# FPGA_IO.net
KiCad netlist of a schematic drawn in Altium Designer
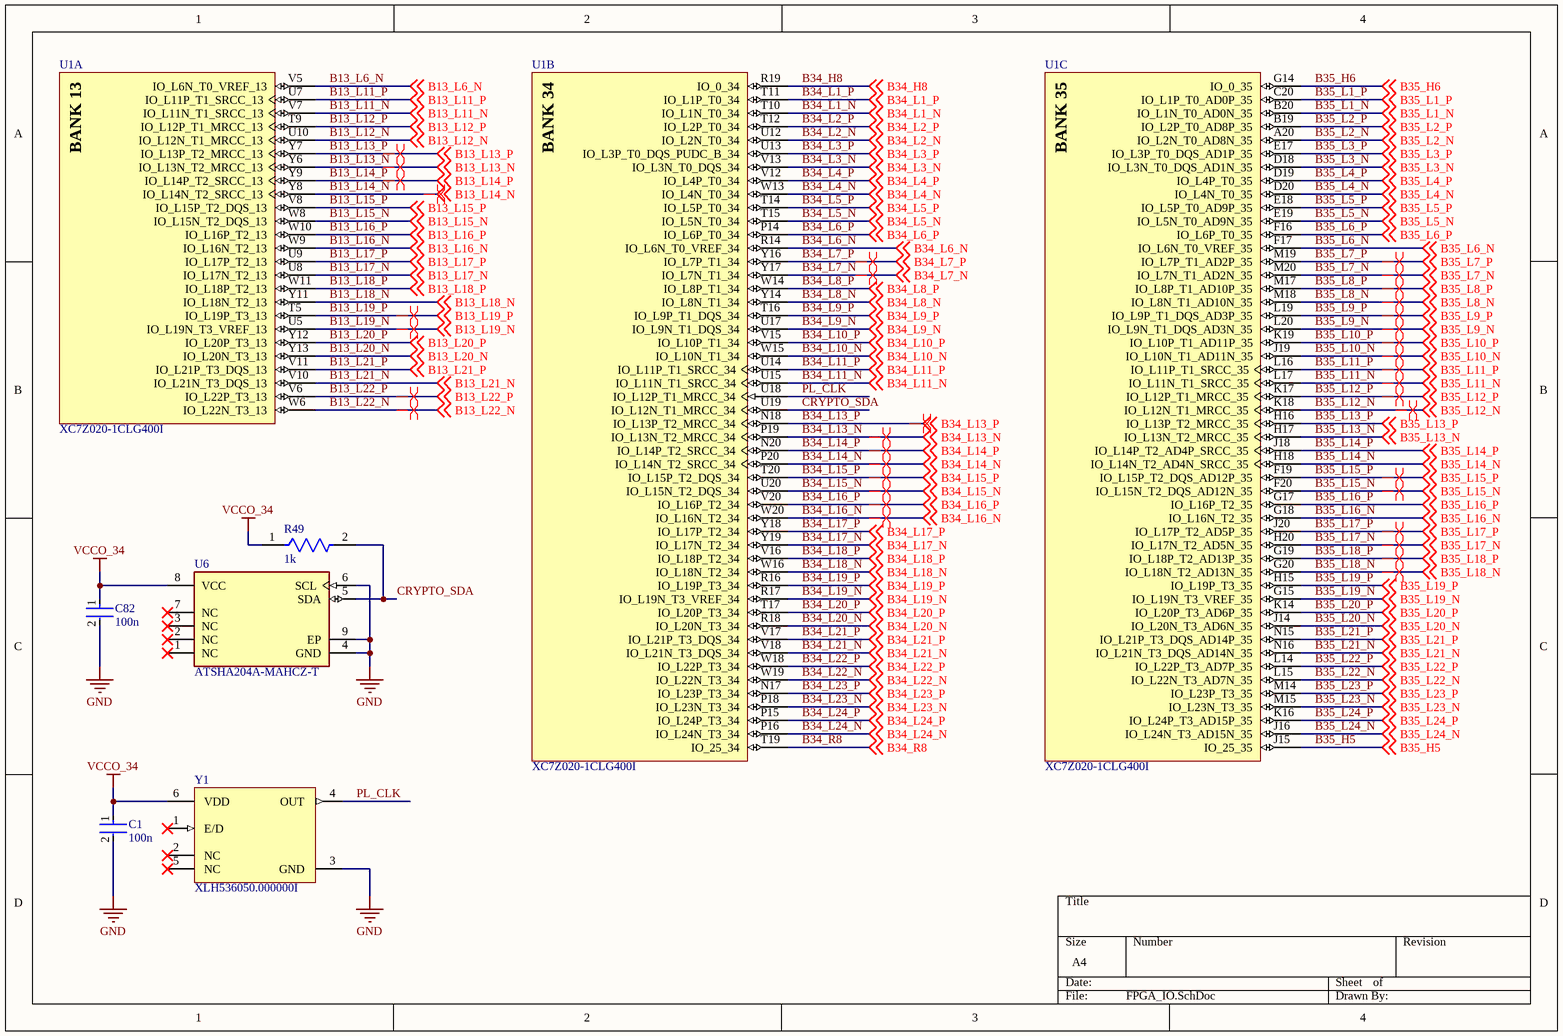
[diagram p0: FPGA_IO.SchDoc]

(export (version "E")
  (design (tool "Eeschema 10.0.6"))
  (components
    (comp (ref "C1")
      (value "100n")
      (footprint "FP-CC0603-DA-MFG")
      (description "CAP CER 0.1UF 50V X7R 0603")
      (fields (field (name "MANUFACTURER") "YAGEO") (field (name "VOLTAGE") "50 V"))
      (libsource (lib "Altium Content Vault") (part "11868f565c42a9108669ba33697ecf6"))
    )
    (comp (ref "C82")
      (value "100n")
      (footprint "FP-CC0603-DA-MFG")
      (description "CAP CER 0.1UF 50V X7R 0603")
      (fields (field (name "MANUFACTURER") "YAGEO") (field (name "VOLTAGE") "50 V"))
      (libsource (lib "Altium Content Vault") (part "11868f565c42a9108669ba33697ecf6"))
    )
    (comp (ref "R49")
      (value "1k")
      (footprint "FP-RC0603-0_55-IPC_C")
      (description "RES 1K OHM 1% 1/10W 0603")
      (fields (field (name "TOLERANCE") "1%"))
      (libsource (lib "Altium Content Vault") (part "1029c3af85768c4190bb7ad29bc67b5"))
    )
    (comp (ref "U1")
      (value "XC7Z020-1CLG400I")
      (footprint "CLG400")
      (fields (field (name "GENERIC PART NUMBER") "XC7Z020"))
      (libsource (lib "Altium Content Vault") (part "XNLX-XC7Z020-CLG400"))
    )
    (comp (ref "U6")
      (value "ATSHA204A-MAHCZ-T")
      (footprint "FP-C04-21355-Q4B-MFG")
      (description "IC AUTHENTICATION CHIP 8UDFN")
      (libsource (lib "Altium Content Vault") (part "d8c86bdfd731f46be08b2b7a0237097"))
    )
    (comp (ref "Y1")
      (value "XLH536050.000000I")
      (footprint "JS6_MFG")
      (description "Oscillator Xo 50MHZ ±25PPM 15PF Hcmos 55% 3.3V 6-PIN Cllcc SMD T/r")
      (libsource (lib "Altium Content Vault") (part "c6c94343aa228214f04837505267066"))
    )
  )
  (nets
    (net (code "1") (name "/CRYPTO_SDA") (class "Default")
      (node (ref "R49") (pin "2") (pinfunction "2_2") (pintype "passive"))
      (node (ref "U1") (pin "U19") (pinfunction "IO_L12N_T1_MRCC_34_U19") (pintype "bidirectional"))
      (node (ref "U6") (pin "5") (pinfunction "SDA_5") (pintype "bidirectional"))
    )
    (net (code "2") (name "/PL_CLK") (class "Default")
      (node (ref "U1") (pin "U18") (pinfunction "IO_L12P_T1_MRCC_34_U18") (pintype "bidirectional"))
      (node (ref "Y1") (pin "4") (pinfunction "OUT_4") (pintype "output"))
    )
    (net (code "3") (name "B13_L6_N") (class "Default")
      (node (ref "U1") (pin "V5") (pinfunction "IO_L6N_T0_VREF_13_V5") (pintype "bidirectional"))
    )
    (net (code "4") (name "B13_L11_N") (class "Default")
      (node (ref "U1") (pin "V7") (pinfunction "IO_L11N_T1_SRCC_13_V7") (pintype "bidirectional"))
    )
    (net (code "5") (name "B13_L11_P") (class "Default")
      (node (ref "U1") (pin "U7") (pinfunction "IO_L11P_T1_SRCC_13_U7") (pintype "bidirectional"))
    )
    (net (code "6") (name "B13_L12_N") (class "Default")
      (node (ref "U1") (pin "U10") (pinfunction "IO_L12N_T1_MRCC_13_U10") (pintype "bidirectional"))
    )
    (net (code "7") (name "B13_L12_P") (class "Default")
      (node (ref "U1") (pin "T9") (pinfunction "IO_L12P_T1_MRCC_13_T9") (pintype "bidirectional"))
    )
    (net (code "8") (name "B13_L13_N") (class "Default")
      (node (ref "U1") (pin "Y6") (pinfunction "IO_L13N_T2_MRCC_13_Y6") (pintype "bidirectional"))
    )
    (net (code "9") (name "B13_L13_P") (class "Default")
      (node (ref "U1") (pin "Y7") (pinfunction "IO_L13P_T2_MRCC_13_Y7") (pintype "bidirectional"))
    )
    (net (code "10") (name "B13_L14_N") (class "Default")
      (node (ref "U1") (pin "Y8") (pinfunction "IO_L14N_T2_SRCC_13_Y8") (pintype "bidirectional"))
    )
    (net (code "11") (name "B13_L14_P") (class "Default")
      (node (ref "U1") (pin "Y9") (pinfunction "IO_L14P_T2_SRCC_13_Y9") (pintype "bidirectional"))
    )
    (net (code "12") (name "B13_L15_N") (class "Default")
      (node (ref "U1") (pin "W8") (pinfunction "IO_L15N_T2_DQS_13_W8") (pintype "bidirectional"))
    )
    (net (code "13") (name "B13_L15_P") (class "Default")
      (node (ref "U1") (pin "V8") (pinfunction "IO_L15P_T2_DQS_13_V8") (pintype "bidirectional"))
    )
    (net (code "14") (name "B13_L16_N") (class "Default")
      (node (ref "U1") (pin "W9") (pinfunction "IO_L16N_T2_13_W9") (pintype "bidirectional"))
    )
    (net (code "15") (name "B13_L16_P") (class "Default")
      (node (ref "U1") (pin "W10") (pinfunction "IO_L16P_T2_13_W10") (pintype "bidirectional"))
    )
    (net (code "16") (name "B13_L17_N") (class "Default")
      (node (ref "U1") (pin "U8") (pinfunction "IO_L17N_T2_13_U8") (pintype "bidirectional"))
    )
    (net (code "17") (name "B13_L17_P") (class "Default")
      (node (ref "U1") (pin "U9") (pinfunction "IO_L17P_T2_13_U9") (pintype "bidirectional"))
    )
    (net (code "18") (name "B13_L18_N") (class "Default")
      (node (ref "U1") (pin "Y11") (pinfunction "IO_L18N_T2_13_Y11") (pintype "bidirectional"))
    )
    (net (code "19") (name "B13_L18_P") (class "Default")
      (node (ref "U1") (pin "W11") (pinfunction "IO_L18P_T2_13_W11") (pintype "bidirectional"))
    )
    (net (code "20") (name "B13_L19_N") (class "Default")
      (node (ref "U1") (pin "U5") (pinfunction "IO_L19N_T3_VREF_13_U5") (pintype "bidirectional"))
    )
    (net (code "21") (name "B13_L19_P") (class "Default")
      (node (ref "U1") (pin "T5") (pinfunction "IO_L19P_T3_13_T5") (pintype "bidirectional"))
    )
    (net (code "22") (name "B13_L20_N") (class "Default")
      (node (ref "U1") (pin "Y13") (pinfunction "IO_L20N_T3_13_Y13") (pintype "bidirectional"))
    )
    (net (code "23") (name "B13_L20_P") (class "Default")
      (node (ref "U1") (pin "Y12") (pinfunction "IO_L20P_T3_13_Y12") (pintype "bidirectional"))
    )
    (net (code "24") (name "B13_L21_N") (class "Default")
      (node (ref "U1") (pin "V10") (pinfunction "IO_L21N_T3_DQS_13_V10") (pintype "bidirectional"))
    )
    (net (code "25") (name "B13_L21_P") (class "Default")
      (node (ref "U1") (pin "V11") (pinfunction "IO_L21P_T3_DQS_13_V11") (pintype "bidirectional"))
    )
    (net (code "26") (name "B13_L22_N") (class "Default")
      (node (ref "U1") (pin "W6") (pinfunction "IO_L22N_T3_13_W6") (pintype "bidirectional"))
    )
    (net (code "27") (name "B13_L22_P") (class "Default")
      (node (ref "U1") (pin "V6") (pinfunction "IO_L22P_T3_13_V6") (pintype "bidirectional"))
    )
    (net (code "28") (name "B34_H8") (class "Default")
      (node (ref "U1") (pin "R19") (pinfunction "IO_0_34_R19") (pintype "bidirectional"))
    )
    (net (code "29") (name "B34_L1_N") (class "Default")
      (node (ref "U1") (pin "T10") (pinfunction "IO_L1N_T0_34_T10") (pintype "bidirectional"))
    )
    (net (code "30") (name "B34_L1_P") (class "Default")
      (node (ref "U1") (pin "T11") (pinfunction "IO_L1P_T0_34_T11") (pintype "bidirectional"))
    )
    (net (code "31") (name "B34_L2_N") (class "Default")
      (node (ref "U1") (pin "U12") (pinfunction "IO_L2N_T0_34_U12") (pintype "bidirectional"))
    )
    (net (code "32") (name "B34_L2_P") (class "Default")
      (node (ref "U1") (pin "T12") (pinfunction "IO_L2P_T0_34_T12") (pintype "bidirectional"))
    )
    (net (code "33") (name "B34_L3_N") (class "Default")
      (node (ref "U1") (pin "V13") (pinfunction "IO_L3N_T0_DQS_34_V13") (pintype "bidirectional"))
    )
    (net (code "34") (name "B34_L3_P") (class "Default")
      (node (ref "U1") (pin "U13") (pinfunction "IO_L3P_T0_DQS_PUDC_B_34_U13") (pintype "bidirectional"))
    )
    (net (code "35") (name "B34_L4_N") (class "Default")
      (node (ref "U1") (pin "W13") (pinfunction "IO_L4N_T0_34_W13") (pintype "bidirectional"))
    )
    (net (code "36") (name "B34_L4_P") (class "Default")
      (node (ref "U1") (pin "V12") (pinfunction "IO_L4P_T0_34_V12") (pintype "bidirectional"))
    )
    (net (code "37") (name "B34_L5_N") (class "Default")
      (node (ref "U1") (pin "T15") (pinfunction "IO_L5N_T0_34_T15") (pintype "bidirectional"))
    )
    (net (code "38") (name "B34_L5_P") (class "Default")
      (node (ref "U1") (pin "T14") (pinfunction "IO_L5P_T0_34_T14") (pintype "bidirectional"))
    )
    (net (code "39") (name "B34_L6_N") (class "Default")
      (node (ref "U1") (pin "R14") (pinfunction "IO_L6N_T0_VREF_34_R14") (pintype "bidirectional"))
    )
    (net (code "40") (name "B34_L6_P") (class "Default")
      (node (ref "U1") (pin "P14") (pinfunction "IO_L6P_T0_34_P14") (pintype "bidirectional"))
    )
    (net (code "41") (name "B34_L7_N") (class "Default")
      (node (ref "U1") (pin "Y17") (pinfunction "IO_L7N_T1_34_Y17") (pintype "bidirectional"))
    )
    (net (code "42") (name "B34_L7_P") (class "Default")
      (node (ref "U1") (pin "Y16") (pinfunction "IO_L7P_T1_34_Y16") (pintype "bidirectional"))
    )
    (net (code "43") (name "B34_L8_N") (class "Default")
      (node (ref "U1") (pin "Y14") (pinfunction "IO_L8N_T1_34_Y14") (pintype "bidirectional"))
    )
    (net (code "44") (name "B34_L8_P") (class "Default")
      (node (ref "U1") (pin "W14") (pinfunction "IO_L8P_T1_34_W14") (pintype "bidirectional"))
    )
    (net (code "45") (name "B34_L9_N") (class "Default")
      (node (ref "U1") (pin "U17") (pinfunction "IO_L9N_T1_DQS_34_U17") (pintype "bidirectional"))
    )
    (net (code "46") (name "B34_L9_P") (class "Default")
      (node (ref "U1") (pin "T16") (pinfunction "IO_L9P_T1_DQS_34_T16") (pintype "bidirectional"))
    )
    (net (code "47") (name "B34_L10_N") (class "Default")
      (node (ref "U1") (pin "W15") (pinfunction "IO_L10N_T1_34_W15") (pintype "bidirectional"))
    )
    (net (code "48") (name "B34_L10_P") (class "Default")
      (node (ref "U1") (pin "V15") (pinfunction "IO_L10P_T1_34_V15") (pintype "bidirectional"))
    )
    (net (code "49") (name "B34_L11_N") (class "Default")
      (node (ref "U1") (pin "U15") (pinfunction "IO_L11N_T1_SRCC_34_U15") (pintype "bidirectional"))
    )
    (net (code "50") (name "B34_L11_P") (class "Default")
      (node (ref "U1") (pin "U14") (pinfunction "IO_L11P_T1_SRCC_34_U14") (pintype "bidirectional"))
    )
    (net (code "51") (name "B34_L13_N") (class "Default")
      (node (ref "U1") (pin "P19") (pinfunction "IO_L13N_T2_MRCC_34_P19") (pintype "bidirectional"))
    )
    (net (code "52") (name "B34_L13_P") (class "Default")
      (node (ref "U1") (pin "N18") (pinfunction "IO_L13P_T2_MRCC_34_N18") (pintype "bidirectional"))
    )
    (net (code "53") (name "B34_L14_N") (class "Default")
      (node (ref "U1") (pin "P20") (pinfunction "IO_L14N_T2_SRCC_34_P20") (pintype "bidirectional"))
    )
    (net (code "54") (name "B34_L14_P") (class "Default")
      (node (ref "U1") (pin "N20") (pinfunction "IO_L14P_T2_SRCC_34_N20") (pintype "bidirectional"))
    )
    (net (code "55") (name "B34_L15_N") (class "Default")
      (node (ref "U1") (pin "U20") (pinfunction "IO_L15N_T2_DQS_34_U20") (pintype "bidirectional"))
    )
    (net (code "56") (name "B34_L15_P") (class "Default")
      (node (ref "U1") (pin "T20") (pinfunction "IO_L15P_T2_DQS_34_T20") (pintype "bidirectional"))
    )
    (net (code "57") (name "B34_L16_N") (class "Default")
      (node (ref "U1") (pin "W20") (pinfunction "IO_L16N_T2_34_W20") (pintype "bidirectional"))
    )
    (net (code "58") (name "B34_L16_P") (class "Default")
      (node (ref "U1") (pin "V20") (pinfunction "IO_L16P_T2_34_V20") (pintype "bidirectional"))
    )
    (net (code "59") (name "B34_L17_N") (class "Default")
      (node (ref "U1") (pin "Y19") (pinfunction "IO_L17N_T2_34_Y19") (pintype "bidirectional"))
    )
    (net (code "60") (name "B34_L17_P") (class "Default")
      (node (ref "U1") (pin "Y18") (pinfunction "IO_L17P_T2_34_Y18") (pintype "bidirectional"))
    )
    (net (code "61") (name "B34_L18_N") (class "Default")
      (node (ref "U1") (pin "W16") (pinfunction "IO_L18N_T2_34_W16") (pintype "bidirectional"))
    )
    (net (code "62") (name "B34_L18_P") (class "Default")
      (node (ref "U1") (pin "V16") (pinfunction "IO_L18P_T2_34_V16") (pintype "bidirectional"))
    )
    (net (code "63") (name "B34_L19_N") (class "Default")
      (node (ref "U1") (pin "R17") (pinfunction "IO_L19N_T3_VREF_34_R17") (pintype "bidirectional"))
    )
    (net (code "64") (name "B34_L19_P") (class "Default")
      (node (ref "U1") (pin "R16") (pinfunction "IO_L19P_T3_34_R16") (pintype "bidirectional"))
    )
    (net (code "65") (name "B34_L20_N") (class "Default")
      (node (ref "U1") (pin "R18") (pinfunction "IO_L20N_T3_34_R18") (pintype "bidirectional"))
    )
    (net (code "66") (name "B34_L20_P") (class "Default")
      (node (ref "U1") (pin "T17") (pinfunction "IO_L20P_T3_34_T17") (pintype "bidirectional"))
    )
    (net (code "67") (name "B34_L21_N") (class "Default")
      (node (ref "U1") (pin "V18") (pinfunction "IO_L21N_T3_DQS_34_V18") (pintype "bidirectional"))
    )
    (net (code "68") (name "B34_L21_P") (class "Default")
      (node (ref "U1") (pin "V17") (pinfunction "IO_L21P_T3_DQS_34_V17") (pintype "bidirectional"))
    )
    (net (code "69") (name "B34_L22_N") (class "Default")
      (node (ref "U1") (pin "W19") (pinfunction "IO_L22N_T3_34_W19") (pintype "bidirectional"))
    )
    (net (code "70") (name "B34_L22_P") (class "Default")
      (node (ref "U1") (pin "W18") (pinfunction "IO_L22P_T3_34_W18") (pintype "bidirectional"))
    )
    (net (code "71") (name "B34_L23_N") (class "Default")
      (node (ref "U1") (pin "P18") (pinfunction "IO_L23N_T3_34_P18") (pintype "bidirectional"))
    )
    (net (code "72") (name "B34_L23_P") (class "Default")
      (node (ref "U1") (pin "N17") (pinfunction "IO_L23P_T3_34_N17") (pintype "bidirectional"))
    )
    (net (code "73") (name "B34_L24_N") (class "Default")
      (node (ref "U1") (pin "P16") (pinfunction "IO_L24N_T3_34_P16") (pintype "bidirectional"))
    )
    (net (code "74") (name "B34_L24_P") (class "Default")
      (node (ref "U1") (pin "P15") (pinfunction "IO_L24P_T3_34_P15") (pintype "bidirectional"))
    )
    (net (code "75") (name "B34_R8") (class "Default")
      (node (ref "U1") (pin "T19") (pinfunction "IO_25_34_T19") (pintype "bidirectional"))
    )
    (net (code "76") (name "B35_H5") (class "Default")
      (node (ref "U1") (pin "J15") (pinfunction "IO_25_35_J15") (pintype "bidirectional"))
    )
    (net (code "77") (name "B35_H6") (class "Default")
      (node (ref "U1") (pin "G14") (pinfunction "IO_0_35_G14") (pintype "bidirectional"))
    )
    (net (code "78") (name "B35_L1_N") (class "Default")
      (node (ref "U1") (pin "B20") (pinfunction "IO_L1N_T0_AD0N_35_B20") (pintype "bidirectional"))
    )
    (net (code "79") (name "B35_L1_P") (class "Default")
      (node (ref "U1") (pin "C20") (pinfunction "IO_L1P_T0_AD0P_35_C20") (pintype "bidirectional"))
    )
    (net (code "80") (name "B35_L2_N") (class "Default")
      (node (ref "U1") (pin "A20") (pinfunction "IO_L2N_T0_AD8N_35_A20") (pintype "bidirectional"))
    )
    (net (code "81") (name "B35_L2_P") (class "Default")
      (node (ref "U1") (pin "B19") (pinfunction "IO_L2P_T0_AD8P_35_B19") (pintype "bidirectional"))
    )
    (net (code "82") (name "B35_L3_N") (class "Default")
      (node (ref "U1") (pin "D18") (pinfunction "IO_L3N_T0_DQS_AD1N_35_D18") (pintype "bidirectional"))
    )
    (net (code "83") (name "B35_L3_P") (class "Default")
      (node (ref "U1") (pin "E17") (pinfunction "IO_L3P_T0_DQS_AD1P_35_E17") (pintype "bidirectional"))
    )
    (net (code "84") (name "B35_L4_N") (class "Default")
      (node (ref "U1") (pin "D20") (pinfunction "IO_L4N_T0_35_D20") (pintype "bidirectional"))
    )
    (net (code "85") (name "B35_L4_P") (class "Default")
      (node (ref "U1") (pin "D19") (pinfunction "IO_L4P_T0_35_D19") (pintype "bidirectional"))
    )
    (net (code "86") (name "B35_L5_N") (class "Default")
      (node (ref "U1") (pin "E19") (pinfunction "IO_L5N_T0_AD9N_35_E19") (pintype "bidirectional"))
    )
    (net (code "87") (name "B35_L5_P") (class "Default")
      (node (ref "U1") (pin "E18") (pinfunction "IO_L5P_T0_AD9P_35_E18") (pintype "bidirectional"))
    )
    (net (code "88") (name "B35_L6_N") (class "Default")
      (node (ref "U1") (pin "F17") (pinfunction "IO_L6N_T0_VREF_35_F17") (pintype "bidirectional"))
    )
    (net (code "89") (name "B35_L6_P") (class "Default")
      (node (ref "U1") (pin "F16") (pinfunction "IO_L6P_T0_35_F16") (pintype "bidirectional"))
    )
    (net (code "90") (name "B35_L7_N") (class "Default")
      (node (ref "U1") (pin "M20") (pinfunction "IO_L7N_T1_AD2N_35_M20") (pintype "bidirectional"))
    )
    (net (code "91") (name "B35_L7_P") (class "Default")
      (node (ref "U1") (pin "M19") (pinfunction "IO_L7P_T1_AD2P_35_M19") (pintype "bidirectional"))
    )
    (net (code "92") (name "B35_L8_N") (class "Default")
      (node (ref "U1") (pin "M18") (pinfunction "IO_L8N_T1_AD10N_35_M18") (pintype "bidirectional"))
    )
    (net (code "93") (name "B35_L8_P") (class "Default")
      (node (ref "U1") (pin "M17") (pinfunction "IO_L8P_T1_AD10P_35_M17") (pintype "bidirectional"))
    )
    (net (code "94") (name "B35_L9_N") (class "Default")
      (node (ref "U1") (pin "L20") (pinfunction "IO_L9N_T1_DQS_AD3N_35_L20") (pintype "bidirectional"))
    )
    (net (code "95") (name "B35_L9_P") (class "Default")
      (node (ref "U1") (pin "L19") (pinfunction "IO_L9P_T1_DQS_AD3P_35_L19") (pintype "bidirectional"))
    )
    (net (code "96") (name "B35_L10_N") (class "Default")
      (node (ref "U1") (pin "J19") (pinfunction "IO_L10N_T1_AD11N_35_J19") (pintype "bidirectional"))
    )
    (net (code "97") (name "B35_L10_P") (class "Default")
      (node (ref "U1") (pin "K19") (pinfunction "IO_L10P_T1_AD11P_35_K19") (pintype "bidirectional"))
    )
    (net (code "98") (name "B35_L11_N") (class "Default")
      (node (ref "U1") (pin "L17") (pinfunction "IO_L11N_T1_SRCC_35_L17") (pintype "bidirectional"))
    )
    (net (code "99") (name "B35_L11_P") (class "Default")
      (node (ref "U1") (pin "L16") (pinfunction "IO_L11P_T1_SRCC_35_L16") (pintype "bidirectional"))
    )
    (net (code "100") (name "B35_L12_N") (class "Default")
      (node (ref "U1") (pin "K18") (pinfunction "IO_L12N_T1_MRCC_35_K18") (pintype "bidirectional"))
    )
    (net (code "101") (name "B35_L12_P") (class "Default")
      (node (ref "U1") (pin "K17") (pinfunction "IO_L12P_T1_MRCC_35_K17") (pintype "bidirectional"))
    )
    (net (code "102") (name "B35_L13_N") (class "Default")
      (node (ref "U1") (pin "H17") (pinfunction "IO_L13N_T2_MRCC_35_H17") (pintype "bidirectional"))
    )
    (net (code "103") (name "B35_L13_P") (class "Default")
      (node (ref "U1") (pin "H16") (pinfunction "IO_L13P_T2_MRCC_35_H16") (pintype "bidirectional"))
    )
    (net (code "104") (name "B35_L14_N") (class "Default")
      (node (ref "U1") (pin "H18") (pinfunction "IO_L14N_T2_AD4N_SRCC_35_H18") (pintype "bidirectional"))
    )
    (net (code "105") (name "B35_L14_P") (class "Default")
      (node (ref "U1") (pin "J18") (pinfunction "IO_L14P_T2_AD4P_SRCC_35_J18") (pintype "bidirectional"))
    )
    (net (code "106") (name "B35_L15_N") (class "Default")
      (node (ref "U1") (pin "F20") (pinfunction "IO_L15N_T2_DQS_AD12N_35_F20") (pintype "bidirectional"))
    )
    (net (code "107") (name "B35_L15_P") (class "Default")
      (node (ref "U1") (pin "F19") (pinfunction "IO_L15P_T2_DQS_AD12P_35_F19") (pintype "bidirectional"))
    )
    (net (code "108") (name "B35_L16_N") (class "Default")
      (node (ref "U1") (pin "G18") (pinfunction "IO_L16N_T2_35_G18") (pintype "bidirectional"))
    )
    (net (code "109") (name "B35_L16_P") (class "Default")
      (node (ref "U1") (pin "G17") (pinfunction "IO_L16P_T2_35_G17") (pintype "bidirectional"))
    )
    (net (code "110") (name "B35_L17_N") (class "Default")
      (node (ref "U1") (pin "H20") (pinfunction "IO_L17N_T2_AD5N_35_H20") (pintype "bidirectional"))
    )
    (net (code "111") (name "B35_L17_P") (class "Default")
      (node (ref "U1") (pin "J20") (pinfunction "IO_L17P_T2_AD5P_35_J20") (pintype "bidirectional"))
    )
    (net (code "112") (name "B35_L18_N") (class "Default")
      (node (ref "U1") (pin "G20") (pinfunction "IO_L18N_T2_AD13N_35_G20") (pintype "bidirectional"))
    )
    (net (code "113") (name "B35_L18_P") (class "Default")
      (node (ref "U1") (pin "G19") (pinfunction "IO_L18P_T2_AD13P_35_G19") (pintype "bidirectional"))
    )
    (net (code "114") (name "B35_L19_N") (class "Default")
      (node (ref "U1") (pin "G15") (pinfunction "IO_L19N_T3_VREF_35_G15") (pintype "bidirectional"))
    )
    (net (code "115") (name "B35_L19_P") (class "Default")
      (node (ref "U1") (pin "H15") (pinfunction "IO_L19P_T3_35_H15") (pintype "bidirectional"))
    )
    (net (code "116") (name "B35_L20_N") (class "Default")
      (node (ref "U1") (pin "J14") (pinfunction "IO_L20N_T3_AD6N_35_J14") (pintype "bidirectional"))
    )
    (net (code "117") (name "B35_L20_P") (class "Default")
      (node (ref "U1") (pin "K14") (pinfunction "IO_L20P_T3_AD6P_35_K14") (pintype "bidirectional"))
    )
    (net (code "118") (name "B35_L21_N") (class "Default")
      (node (ref "U1") (pin "N16") (pinfunction "IO_L21N_T3_DQS_AD14N_35_N16") (pintype "bidirectional"))
    )
    (net (code "119") (name "B35_L21_P") (class "Default")
      (node (ref "U1") (pin "N15") (pinfunction "IO_L21P_T3_DQS_AD14P_35_N15") (pintype "bidirectional"))
    )
    (net (code "120") (name "B35_L22_N") (class "Default")
      (node (ref "U1") (pin "L15") (pinfunction "IO_L22N_T3_AD7N_35_L15") (pintype "bidirectional"))
    )
    (net (code "121") (name "B35_L22_P") (class "Default")
      (node (ref "U1") (pin "L14") (pinfunction "IO_L22P_T3_AD7P_35_L14") (pintype "bidirectional"))
    )
    (net (code "122") (name "B35_L23_N") (class "Default")
      (node (ref "U1") (pin "M15") (pinfunction "IO_L23N_T3_35_M15") (pintype "bidirectional"))
    )
    (net (code "123") (name "B35_L23_P") (class "Default")
      (node (ref "U1") (pin "M14") (pinfunction "IO_L23P_T3_35_M14") (pintype "bidirectional"))
    )
    (net (code "124") (name "B35_L24_N") (class "Default")
      (node (ref "U1") (pin "J16") (pinfunction "IO_L24N_T3_AD15N_35_J16") (pintype "bidirectional"))
    )
    (net (code "125") (name "B35_L24_P") (class "Default")
      (node (ref "U1") (pin "K16") (pinfunction "IO_L24P_T3_AD15P_35_K16") (pintype "bidirectional"))
    )
    (net (code "126") (name "GND") (class "Default")
      (node (ref "C1") (pin "2") (pinfunction "2_2") (pintype "passive"))
      (node (ref "C82") (pin "2") (pinfunction "2_2") (pintype "passive"))
      (node (ref "U6") (pin "4") (pinfunction "GND_4") (pintype "power_in"))
      (node (ref "U6") (pin "6") (pinfunction "SCL_6") (pintype "input"))
      (node (ref "U6") (pin "9") (pinfunction "EP_9") (pintype "passive"))
      (node (ref "Y1") (pin "3") (pinfunction "GND_3") (pintype "power_in"))
    )
    (net (code "127") (name "VCCO_34") (class "Default")
      (node (ref "C1") (pin "1") (pinfunction "1_1") (pintype "passive"))
      (node (ref "C82") (pin "1") (pinfunction "1_1") (pintype "passive"))
      (node (ref "R49") (pin "1") (pinfunction "1_1") (pintype "passive"))
      (node (ref "U6") (pin "8") (pinfunction "VCC_8") (pintype "power_in"))
      (node (ref "Y1") (pin "6") (pinfunction "VDD_6") (pintype "power_in"))
    )
    (net (code "128") (name "unconnected-(U6-NC-Pad1)") (class "Default")
      (node (ref "U6") (pin "1") (pinfunction "NC_1") (pintype "passive+no_connect"))
    )
    (net (code "129") (name "unconnected-(U6-NC-Pad2)") (class "Default")
      (node (ref "U6") (pin "2") (pinfunction "NC_2") (pintype "passive+no_connect"))
    )
    (net (code "130") (name "unconnected-(U6-NC-Pad3)") (class "Default")
      (node (ref "U6") (pin "3") (pinfunction "NC_3") (pintype "passive+no_connect"))
    )
    (net (code "131") (name "unconnected-(U6-NC-Pad7)") (class "Default")
      (node (ref "U6") (pin "7") (pinfunction "NC_7") (pintype "passive+no_connect"))
    )
    (net (code "132") (name "unconnected-(Y1-E{slash}D-Pad1)") (class "Default")
      (node (ref "Y1") (pin "1") (pinfunction "E/D_1") (pintype "input+no_connect"))
    )
    (net (code "133") (name "unconnected-(Y1-NC-Pad2)") (class "Default")
      (node (ref "Y1") (pin "2") (pinfunction "NC_2") (pintype "passive+no_connect"))
    )
    (net (code "134") (name "unconnected-(Y1-NC-Pad5)") (class "Default")
      (node (ref "Y1") (pin "5") (pinfunction "NC_5") (pintype "passive+no_connect"))
    )
  )
)
